# steerstick_power.net
KiCad netlist of a schematic drawn in EAGLE
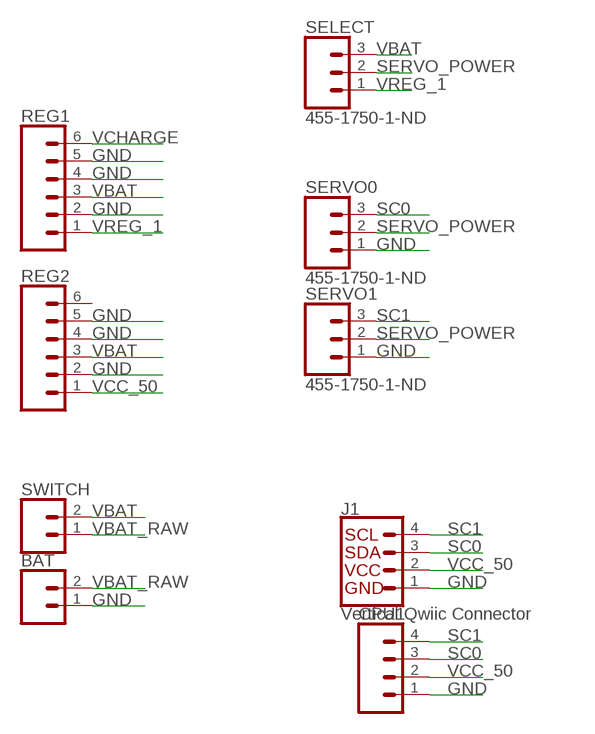
[diagram p0: schematic, sheet 1]

(export (version "E")
  (design (tool "Eeschema 10.0.6"))
  (components
    (comp (ref "BAT")
      (value "CONN_02")
      (footprint "eagle-import:1X02")
      (libsource (lib "eagle-import") (part "CONN_02"))
    )
    (comp (ref "CPU1")
      (value "CONN_041X04_NO_SILK")
      (footprint "eagle-import:1X04_NO_SILK")
      (libsource (lib "eagle-import") (part "CONN_041X04_NO_SILK"))
    )
    (comp (ref "J1")
      (value "Vertical Qwiic Connector")
      (footprint "eagle-import:JST04_1MM_VERT")
      (libsource (lib "eagle-import") (part "QWIIC_CONNECTOR"))
    )
    (comp (ref "REG1")
      (value "CONN_06SILK_FEMALE_PTH")
      (footprint "eagle-import:1X06")
      (libsource (lib "eagle-import") (part "CONN_06SILK_FEMALE_PTH"))
    )
    (comp (ref "REG2")
      (value "CONN_06SILK_FEMALE_PTH")
      (footprint "eagle-import:1X06")
      (libsource (lib "eagle-import") (part "CONN_06SILK_FEMALE_PTH"))
    )
    (comp (ref "SELECT")
      (value "455-1750-1-ND")
      (footprint "eagle-import:1X03")
      (libsource (lib "eagle-import") (part "CONN_03"))
    )
    (comp (ref "SERVO0")
      (value "455-1750-1-ND")
      (footprint "eagle-import:1X03")
      (libsource (lib "eagle-import") (part "CONN_03"))
    )
    (comp (ref "SERVO1")
      (value "455-1750-1-ND")
      (footprint "eagle-import:1X03")
      (libsource (lib "eagle-import") (part "CONN_03"))
    )
    (comp (ref "SWITCH")
      (value "CONN_02")
      (footprint "eagle-import:1X02")
      (libsource (lib "eagle-import") (part "CONN_02"))
    )
  )
  (nets
    (net (code "1") (name "/GND") (class "Default")
      (node (ref "BAT") (pin "1") (pinfunction "1_1") (pintype "passive"))
      (node (ref "CPU1") (pin "1") (pinfunction "1_1") (pintype "passive"))
      (node (ref "J1") (pin "1") (pinfunction "1_1") (pintype "power_in"))
      (node (ref "REG1") (pin "2") (pinfunction "2_2") (pintype "passive"))
      (node (ref "REG1") (pin "4") (pinfunction "4_4") (pintype "passive"))
      (node (ref "REG1") (pin "5") (pinfunction "5_5") (pintype "passive"))
      (node (ref "REG2") (pin "2") (pinfunction "2_2") (pintype "passive"))
      (node (ref "REG2") (pin "4") (pinfunction "4_4") (pintype "passive"))
      (node (ref "REG2") (pin "5") (pinfunction "5_5") (pintype "passive"))
      (node (ref "SERVO0") (pin "1") (pinfunction "1_1") (pintype "passive"))
      (node (ref "SERVO1") (pin "1") (pinfunction "1_1") (pintype "passive"))
    )
    (net (code "2") (name "/SC0") (class "Default")
      (node (ref "CPU1") (pin "3") (pinfunction "3_3") (pintype "passive"))
      (node (ref "J1") (pin "3") (pinfunction "3_3") (pintype "passive"))
      (node (ref "SERVO0") (pin "3") (pinfunction "3_3") (pintype "passive"))
    )
    (net (code "3") (name "/SC1") (class "Default")
      (node (ref "CPU1") (pin "4") (pinfunction "4_4") (pintype "passive"))
      (node (ref "J1") (pin "4") (pinfunction "4_4") (pintype "passive"))
      (node (ref "SERVO1") (pin "3") (pinfunction "3_3") (pintype "passive"))
    )
    (net (code "4") (name "/SERVO_POWER") (class "Default")
      (node (ref "SELECT") (pin "2") (pinfunction "2_2") (pintype "passive"))
      (node (ref "SERVO0") (pin "2") (pinfunction "2_2") (pintype "passive"))
      (node (ref "SERVO1") (pin "2") (pinfunction "2_2") (pintype "passive"))
    )
    (net (code "5") (name "/VBAT") (class "Default")
      (node (ref "REG1") (pin "3") (pinfunction "3_3") (pintype "passive"))
      (node (ref "REG2") (pin "3") (pinfunction "3_3") (pintype "passive"))
      (node (ref "SELECT") (pin "3") (pinfunction "3_3") (pintype "passive"))
      (node (ref "SWITCH") (pin "2") (pinfunction "2_2") (pintype "passive"))
    )
    (net (code "6") (name "/VBAT_RAW") (class "Default")
      (node (ref "BAT") (pin "2") (pinfunction "2_2") (pintype "passive"))
      (node (ref "SWITCH") (pin "1") (pinfunction "1_1") (pintype "passive"))
    )
    (net (code "7") (name "/VCC_50") (class "Default")
      (node (ref "CPU1") (pin "2") (pinfunction "2_2") (pintype "passive"))
      (node (ref "J1") (pin "2") (pinfunction "2_2") (pintype "power_in"))
      (node (ref "REG2") (pin "1") (pinfunction "1_1") (pintype "passive"))
    )
    (net (code "8") (name "/VCHARGE") (class "Default")
      (node (ref "REG1") (pin "6") (pinfunction "6_6") (pintype "passive"))
    )
    (net (code "9") (name "/VREG_1") (class "Default")
      (node (ref "REG1") (pin "1") (pinfunction "1_1") (pintype "passive"))
      (node (ref "SELECT") (pin "1") (pinfunction "1_1") (pintype "passive"))
    )
    (net (code "10") (name "unconnected-(REG2-Pad6)") (class "Default")
      (node (ref "REG2") (pin "6") (pinfunction "6_6") (pintype "passive"))
    )
  )
)
